# hexasense.net
KiCad netlist of a schematic drawn in EAGLE
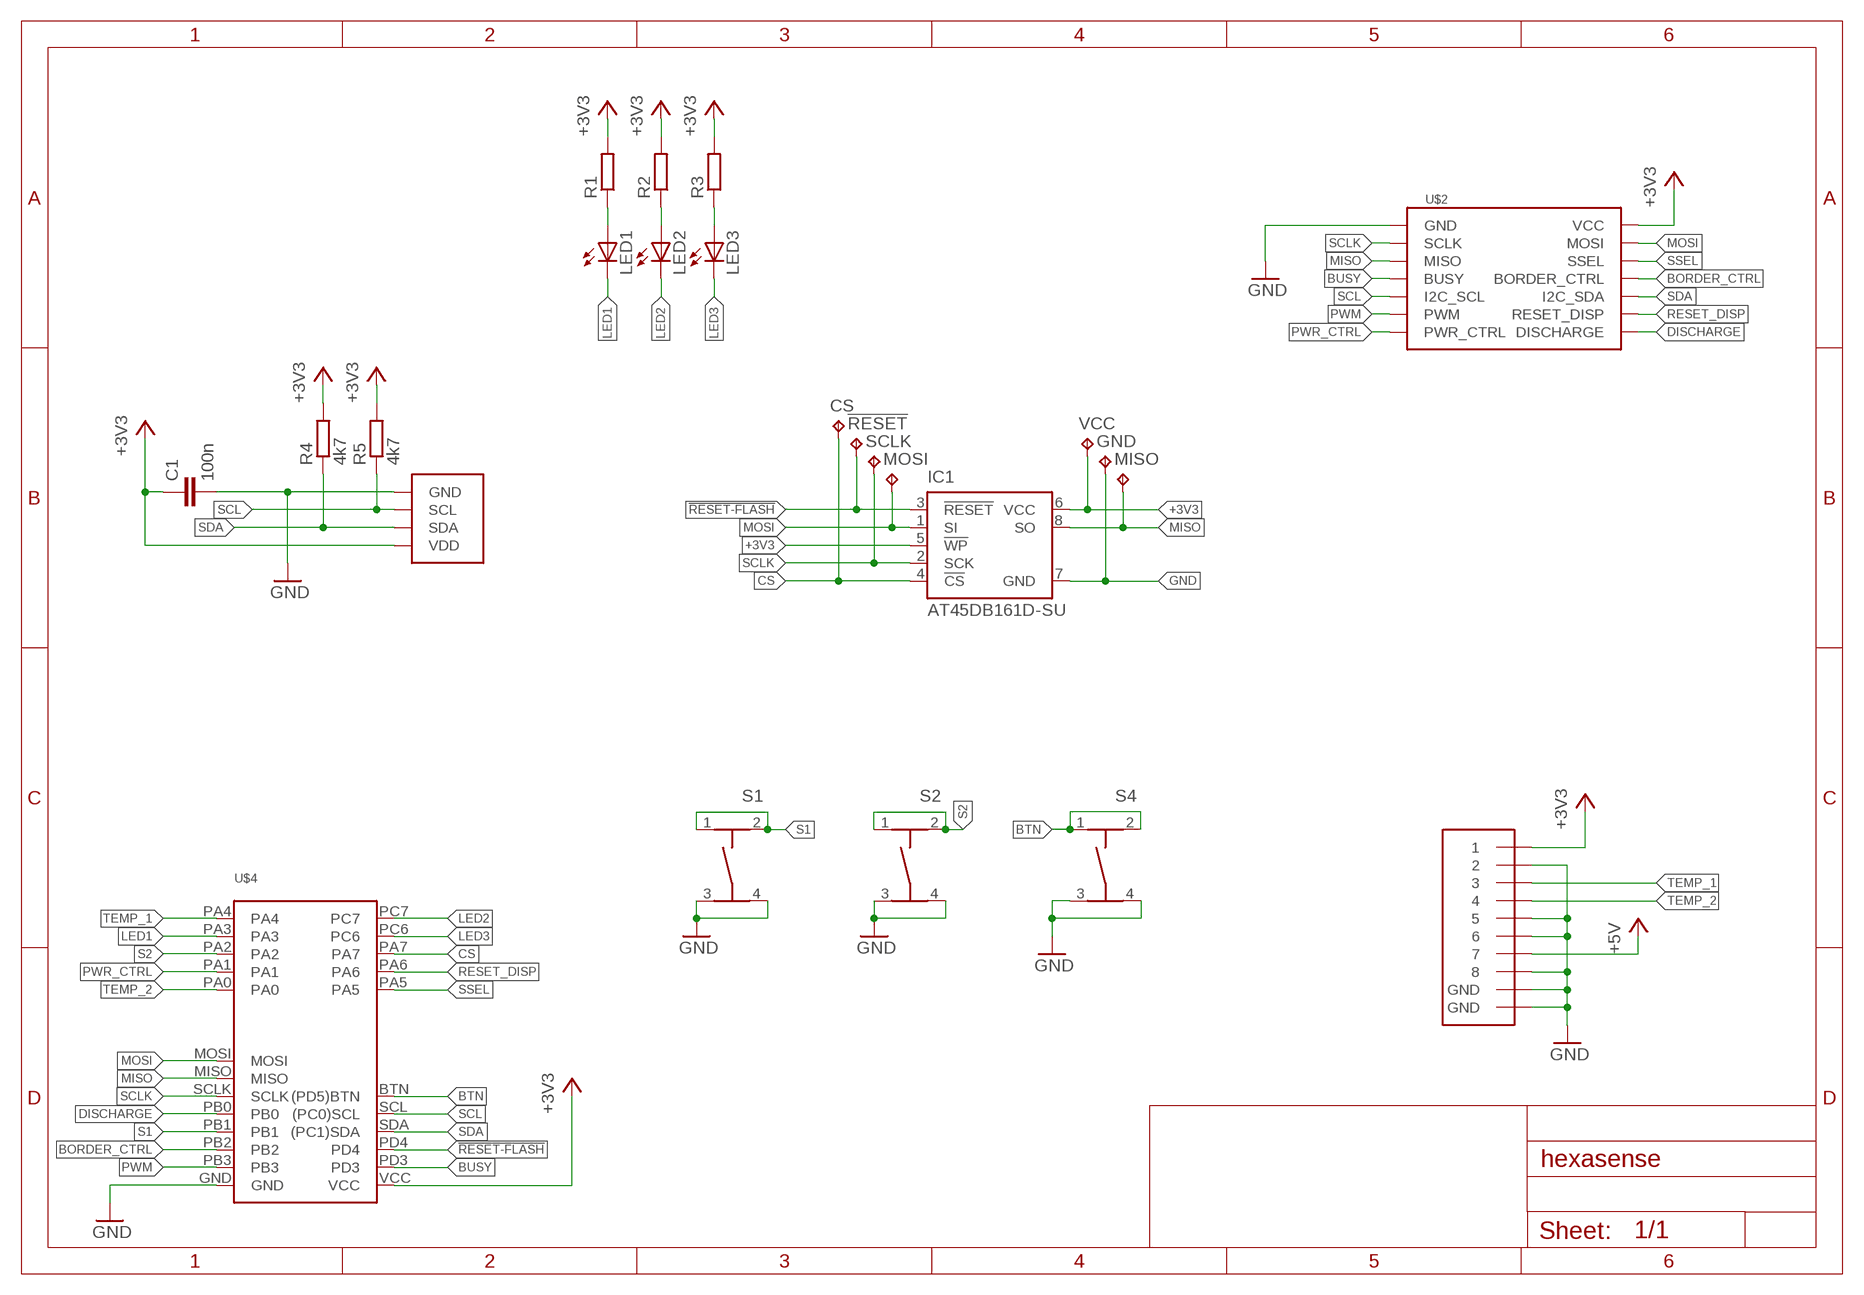
[diagram p0: schematic, sheet 1]

(export (version "E")
  (design (tool "Eeschema 10.0.6"))
  (components
    (comp (ref "!RESET")
      (value "TPB1,27")
      (footprint "eagle-import:B1,27")
      (libsource (lib "eagle-import") (part "TPB1,27"))
    )
    (comp (ref "C1")
      (value "100n")
      (footprint "eagle-import:C0805")
      (libsource (lib "eagle-import") (part "C-EUC0805"))
    )
    (comp (ref "CS")
      (value "TPB1,27")
      (footprint "eagle-import:B1,27")
      (libsource (lib "eagle-import") (part "TPB1,27"))
    )
    (comp (ref "GND")
      (value "TPB1,27")
      (footprint "eagle-import:B1,27")
      (libsource (lib "eagle-import") (part "TPB1,27"))
    )
    (comp (ref "IC1")
      (value "AT45DB161D-SU")
      (footprint "eagle-import:8S2")
      (fields (field (name "MF") "ATMEL"))
      (libsource (lib "eagle-import") (part "AT45DB161D-SU"))
    )
    (comp (ref "LED1")
      (value "LED3MM")
      (footprint "eagle-import:LED3MM")
      (libsource (lib "eagle-import") (part "LED3MM"))
    )
    (comp (ref "LED2")
      (value "LED3MM")
      (footprint "eagle-import:LED3MM")
      (libsource (lib "eagle-import") (part "LED3MM"))
    )
    (comp (ref "LED3")
      (value "LED3MM")
      (footprint "eagle-import:LED3MM")
      (libsource (lib "eagle-import") (part "LED3MM"))
    )
    (comp (ref "MISO")
      (value "TPB1,27")
      (footprint "eagle-import:B1,27")
      (libsource (lib "eagle-import") (part "TPB1,27"))
    )
    (comp (ref "MOSI")
      (value "TPB1,27")
      (footprint "eagle-import:B1,27")
      (libsource (lib "eagle-import") (part "TPB1,27"))
    )
    (comp (ref "R1")
      (value "R-EU_R0805")
      (footprint "eagle-import:R0805")
      (libsource (lib "eagle-import") (part "R-EU_R0805"))
    )
    (comp (ref "R2")
      (value "R-EU_R0805")
      (footprint "eagle-import:R0805")
      (libsource (lib "eagle-import") (part "R-EU_R0805"))
    )
    (comp (ref "R3")
      (value "R-EU_R0805")
      (footprint "eagle-import:R0805")
      (libsource (lib "eagle-import") (part "R-EU_R0805"))
    )
    (comp (ref "R4")
      (value "4k7")
      (footprint "eagle-import:R0805")
      (libsource (lib "eagle-import") (part "R-EU_R0805"))
    )
    (comp (ref "R5")
      (value "4k7")
      (footprint "eagle-import:R0805")
      (libsource (lib "eagle-import") (part "R-EU_R0805"))
    )
    (comp (ref "S1")
      (value "TASTER-9314_SMD")
      (footprint "eagle-import:TASTER-9314_SMD")
      (libsource (lib "eagle-import") (part "TASTER-9314_SMD"))
    )
    (comp (ref "S2")
      (value "TASTER-9314_SMD")
      (footprint "eagle-import:TASTER-9314_SMD")
      (libsource (lib "eagle-import") (part "TASTER-9314_SMD"))
    )
    (comp (ref "S4")
      (value "TASTER-9314_SMD")
      (footprint "eagle-import:TASTER-9314_SMD")
      (libsource (lib "eagle-import") (part "TASTER-9314_SMD"))
    )
    (comp (ref "SCLK")
      (value "TPB1,27")
      (footprint "eagle-import:B1,27")
      (libsource (lib "eagle-import") (part "TPB1,27"))
    )
    (comp (ref "U$1")
      (value "MEBP8-8G")
      (footprint "eagle-import:RJ45-REICHELT")
      (libsource (lib "eagle-import") (part "MEBP8-8G"))
    )
    (comp (ref "U$2")
      (value "EPAPER")
      (footprint "eagle-import:EPAPER")
      (libsource (lib "eagle-import") (part "EPAPER"))
    )
    (comp (ref "U$4")
      (value "HEXABUS")
      (footprint "eagle-import:HEXABUS")
      (libsource (lib "eagle-import") (part "HEXABUS"))
    )
    (comp (ref "U$7")
      (value "HYT271")
      (footprint "eagle-import:HYT271")
      (libsource (lib "eagle-import") (part "HYT271"))
    )
    (comp (ref "VCC")
      (value "TPB1,27")
      (footprint "eagle-import:B1,27")
      (libsource (lib "eagle-import") (part "TPB1,27"))
    )
  )
  (nets
    (net (code "1") (name "+3V3") (class "Default")
      (node (ref "C1") (pin "1") (pinfunction "1_1") (pintype "passive"))
      (node (ref "IC1") (pin "5") (pinfunction "~{WP}_5") (pintype "input"))
      (node (ref "IC1") (pin "6") (pinfunction "VCC_6") (pintype "power_in"))
      (node (ref "R1") (pin "2") (pinfunction "2_2") (pintype "passive"))
      (node (ref "R2") (pin "2") (pinfunction "2_2") (pintype "passive"))
      (node (ref "R3") (pin "2") (pinfunction "2_2") (pintype "passive"))
      (node (ref "R4") (pin "2") (pinfunction "2_2") (pintype "passive"))
      (node (ref "R5") (pin "2") (pinfunction "2_2") (pintype "passive"))
      (node (ref "U$1") (pin "1") (pinfunction "1_1") (pintype "bidirectional"))
      (node (ref "U$2") (pin "P2") (pinfunction "VCC_P2") (pintype "power_in"))
      (node (ref "U$4") (pin "VCC") (pinfunction "VCC_VCC") (pintype "bidirectional"))
      (node (ref "U$7") (pin "VDD") (pinfunction "VDD_VDD") (pintype "power_in"))
      (node (ref "VCC") (pin "TP") (pinfunction "TP_TP") (pintype "input"))
    )
    (net (code "2") (name "+5V") (class "Default")
      (node (ref "U$1") (pin "7") (pinfunction "7_7") (pintype "bidirectional"))
    )
    (net (code "3") (name "/~{RESET-FLASH}") (class "Default")
      (node (ref "!RESET") (pin "TP") (pinfunction "TP_TP") (pintype "input"))
      (node (ref "IC1") (pin "3") (pinfunction "~{RESET}_3") (pintype "input"))
      (node (ref "U$4") (pin "PD4") (pinfunction "PD4_PD4") (pintype "bidirectional"))
    )
    (net (code "4") (name "BORDER_CTRL") (class "Default")
      (node (ref "U$2") (pin "P8") (pinfunction "BORDER_CTRL_P8") (pintype "bidirectional"))
      (node (ref "U$4") (pin "PB2") (pinfunction "PB2_PB2") (pintype "bidirectional"))
    )
    (net (code "5") (name "BTN") (class "Default")
      (node (ref "S4") (pin "1") (pinfunction "1_1") (pintype "passive"))
      (node (ref "S4") (pin "2") (pinfunction "2_2") (pintype "passive"))
      (node (ref "U$4") (pin "BTN") (pinfunction "(PD5)BTN_BTN") (pintype "bidirectional"))
    )
    (net (code "6") (name "BUSY") (class "Default")
      (node (ref "U$2") (pin "P7") (pinfunction "BUSY_P7") (pintype "bidirectional"))
      (node (ref "U$4") (pin "PD3") (pinfunction "PD3_PD3") (pintype "bidirectional"))
    )
    (net (code "7") (name "CS") (class "Default")
      (node (ref "CS") (pin "TP") (pinfunction "TP_TP") (pintype "input"))
      (node (ref "IC1") (pin "4") (pinfunction "~{CS}_4") (pintype "input"))
      (node (ref "U$4") (pin "PA7") (pinfunction "PA7_PA7") (pintype "bidirectional"))
    )
    (net (code "8") (name "DISCHARGE") (class "Default")
      (node (ref "U$2") (pin "P14") (pinfunction "DISCHARGE_P14") (pintype "bidirectional"))
      (node (ref "U$4") (pin "PB0") (pinfunction "PB0_PB0") (pintype "bidirectional"))
    )
    (net (code "9") (name "GND") (class "Default")
      (node (ref "C1") (pin "2") (pinfunction "2_2") (pintype "passive"))
      (node (ref "GND") (pin "TP") (pinfunction "TP_TP") (pintype "input"))
      (node (ref "IC1") (pin "7") (pinfunction "GND_7") (pintype "power_in"))
      (node (ref "S1") (pin "3") (pinfunction "3_3") (pintype "passive"))
      (node (ref "S1") (pin "4") (pinfunction "4_4") (pintype "passive"))
      (node (ref "S2") (pin "3") (pinfunction "3_3") (pintype "passive"))
      (node (ref "S2") (pin "4") (pinfunction "4_4") (pintype "passive"))
      (node (ref "S4") (pin "3") (pinfunction "3_3") (pintype "passive"))
      (node (ref "S4") (pin "4") (pinfunction "4_4") (pintype "passive"))
      (node (ref "U$1") (pin "2") (pinfunction "2_2") (pintype "bidirectional"))
      (node (ref "U$1") (pin "5") (pinfunction "5_5") (pintype "bidirectional"))
      (node (ref "U$1") (pin "6") (pinfunction "6_6") (pintype "bidirectional"))
      (node (ref "U$1") (pin "8") (pinfunction "8_8") (pintype "bidirectional"))
      (node (ref "U$1") (pin "GND@1") (pinfunction "GND_GND@1") (pintype "power_in"))
      (node (ref "U$1") (pin "GND@2") (pinfunction "GND_GND@2") (pintype "power_in"))
      (node (ref "U$2") (pin "P1") (pinfunction "GND_P1") (pintype "power_in"))
      (node (ref "U$4") (pin "GND") (pinfunction "GND_GND") (pintype "bidirectional"))
      (node (ref "U$7") (pin "GND") (pinfunction "GND_GND") (pintype "power_in"))
    )
    (net (code "10") (name "LED1") (class "Default")
      (node (ref "LED1") (pin "K") (pinfunction "C_K") (pintype "passive"))
      (node (ref "U$4") (pin "PA3") (pinfunction "PA3_PA3") (pintype "bidirectional"))
    )
    (net (code "11") (name "LED2") (class "Default")
      (node (ref "LED2") (pin "K") (pinfunction "C_K") (pintype "passive"))
      (node (ref "U$4") (pin "PC7") (pinfunction "PC7_PC7") (pintype "bidirectional"))
    )
    (net (code "12") (name "LED3") (class "Default")
      (node (ref "LED3") (pin "K") (pinfunction "C_K") (pintype "passive"))
      (node (ref "U$4") (pin "PC6") (pinfunction "PC6_PC6") (pintype "bidirectional"))
    )
    (net (code "13") (name "MISO") (class "Default")
      (node (ref "IC1") (pin "8") (pinfunction "SO_8") (pintype "output"))
      (node (ref "MISO") (pin "TP") (pinfunction "TP_TP") (pintype "input"))
      (node (ref "U$2") (pin "P5") (pinfunction "MISO_P5") (pintype "bidirectional"))
      (node (ref "U$4") (pin "MISO") (pinfunction "MISO_MISO") (pintype "bidirectional"))
    )
    (net (code "14") (name "MOSI") (class "Default")
      (node (ref "IC1") (pin "1") (pinfunction "SI_1") (pintype "input"))
      (node (ref "MOSI") (pin "TP") (pinfunction "TP_TP") (pintype "input"))
      (node (ref "U$2") (pin "P4") (pinfunction "MOSI_P4") (pintype "bidirectional"))
      (node (ref "U$4") (pin "MOSI") (pinfunction "MOSI_MOSI") (pintype "bidirectional"))
    )
    (net (code "15") (name "Net-(LED1-PadA)") (class "Default")
      (node (ref "LED1") (pin "A") (pinfunction "A_A") (pintype "passive"))
      (node (ref "R1") (pin "1") (pinfunction "1_1") (pintype "passive"))
    )
    (net (code "16") (name "Net-(LED2-PadA)") (class "Default")
      (node (ref "LED2") (pin "A") (pinfunction "A_A") (pintype "passive"))
      (node (ref "R2") (pin "1") (pinfunction "1_1") (pintype "passive"))
    )
    (net (code "17") (name "Net-(LED3-PadA)") (class "Default")
      (node (ref "LED3") (pin "A") (pinfunction "A_A") (pintype "passive"))
      (node (ref "R3") (pin "1") (pinfunction "1_1") (pintype "passive"))
    )
    (net (code "18") (name "PWM") (class "Default")
      (node (ref "U$2") (pin "P11") (pinfunction "PWM_P11") (pintype "bidirectional"))
      (node (ref "U$4") (pin "PB3") (pinfunction "PB3_PB3") (pintype "bidirectional"))
    )
    (net (code "19") (name "PWR_CTRL") (class "Default")
      (node (ref "U$2") (pin "P13") (pinfunction "PWR_CTRL_P13") (pintype "bidirectional"))
      (node (ref "U$4") (pin "PA1") (pinfunction "PA1_PA1") (pintype "bidirectional"))
    )
    (net (code "20") (name "RESET_DISP") (class "Default")
      (node (ref "U$2") (pin "P12") (pinfunction "RESET_DISP_P12") (pintype "bidirectional"))
      (node (ref "U$4") (pin "PA6") (pinfunction "PA6_PA6") (pintype "bidirectional"))
    )
    (net (code "21") (name "S1") (class "Default")
      (node (ref "S1") (pin "1") (pinfunction "1_1") (pintype "passive"))
      (node (ref "S1") (pin "2") (pinfunction "2_2") (pintype "passive"))
      (node (ref "U$4") (pin "PB1") (pinfunction "PB1_PB1") (pintype "bidirectional"))
    )
    (net (code "22") (name "S2") (class "Default")
      (node (ref "S2") (pin "1") (pinfunction "1_1") (pintype "passive"))
      (node (ref "S2") (pin "2") (pinfunction "2_2") (pintype "passive"))
      (node (ref "U$4") (pin "PA2") (pinfunction "PA2_PA2") (pintype "bidirectional"))
    )
    (net (code "23") (name "SCL") (class "Default")
      (node (ref "R5") (pin "1") (pinfunction "1_1") (pintype "passive"))
      (node (ref "U$2") (pin "P9") (pinfunction "I2C_SCL_P9") (pintype "bidirectional"))
      (node (ref "U$4") (pin "SCL") (pinfunction "(PC0)SCL_SCL") (pintype "bidirectional"))
      (node (ref "U$7") (pin "SCL") (pinfunction "SCL_SCL") (pintype "bidirectional"))
    )
    (net (code "24") (name "SCLK") (class "Default")
      (node (ref "IC1") (pin "2") (pinfunction "SCK_2") (pintype "input"))
      (node (ref "SCLK") (pin "TP") (pinfunction "TP_TP") (pintype "input"))
      (node (ref "U$2") (pin "P3") (pinfunction "SCLK_P3") (pintype "bidirectional"))
      (node (ref "U$4") (pin "SCLK") (pinfunction "SCLK_SCLK") (pintype "bidirectional"))
    )
    (net (code "25") (name "SDA") (class "Default")
      (node (ref "R4") (pin "1") (pinfunction "1_1") (pintype "passive"))
      (node (ref "U$2") (pin "P10") (pinfunction "I2C_SDA_P10") (pintype "bidirectional"))
      (node (ref "U$4") (pin "SDA") (pinfunction "(PC1)SDA_SDA") (pintype "bidirectional"))
      (node (ref "U$7") (pin "SDA") (pinfunction "SDA_SDA") (pintype "bidirectional"))
    )
    (net (code "26") (name "SSEL") (class "Default")
      (node (ref "U$2") (pin "P6") (pinfunction "SSEL_P6") (pintype "bidirectional"))
      (node (ref "U$4") (pin "PA5") (pinfunction "PA5_PA5") (pintype "bidirectional"))
    )
    (net (code "27") (name "TEMP_1") (class "Default")
      (node (ref "U$1") (pin "3") (pinfunction "3_3") (pintype "bidirectional"))
      (node (ref "U$4") (pin "PA4") (pinfunction "PA4_PA4") (pintype "bidirectional"))
    )
    (net (code "28") (name "TEMP_2") (class "Default")
      (node (ref "U$1") (pin "4") (pinfunction "4_4") (pintype "bidirectional"))
      (node (ref "U$4") (pin "PA0") (pinfunction "PA0_PA0") (pintype "bidirectional"))
    )
  )
)
